# cv-display.net
KiCad netlist of a schematic drawn in EAGLE
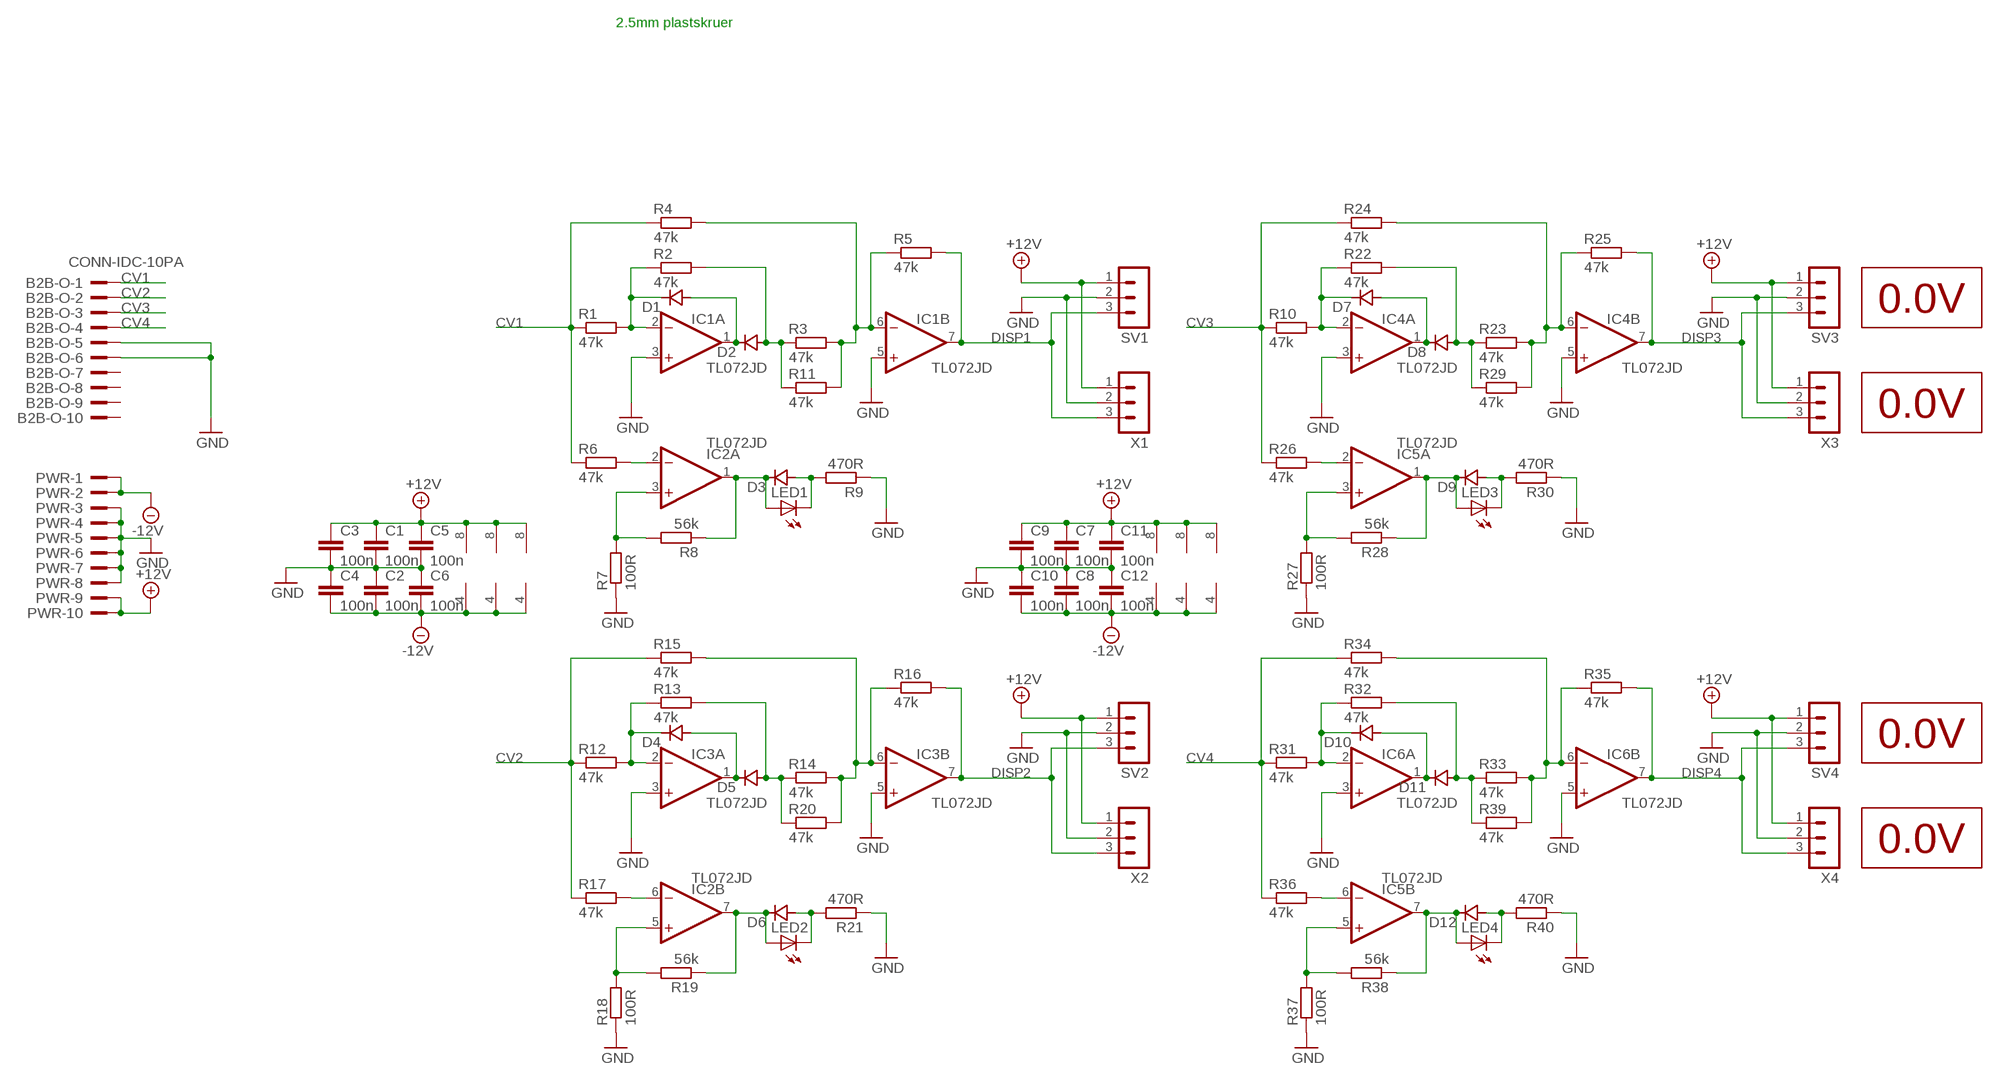
[diagram p0: schematic, sheet 1]

(export (version "E")
  (design (tool "Eeschema 10.0.6"))
  (components
    (comp (ref "B2B-O")
      (value "CONN-IDC-10PA")
      (footprint "eagle-import:CONN-IDC10P-A")
      (libsource (lib "eagle-import") (part "CONN-IDC-10PA"))
    )
    (comp (ref "C1")
      (value "100n")
      (footprint "eagle-import:C0603")
      (libsource (lib "eagle-import") (part "C-EUC0603"))
    )
    (comp (ref "C2")
      (value "100n")
      (footprint "eagle-import:C0603")
      (libsource (lib "eagle-import") (part "C-EUC0603"))
    )
    (comp (ref "C3")
      (value "100n")
      (footprint "eagle-import:C0603")
      (libsource (lib "eagle-import") (part "C-EUC0603"))
    )
    (comp (ref "C4")
      (value "100n")
      (footprint "eagle-import:C0603")
      (libsource (lib "eagle-import") (part "C-EUC0603"))
    )
    (comp (ref "C5")
      (value "100n")
      (footprint "eagle-import:C0603")
      (libsource (lib "eagle-import") (part "C-EUC0603"))
    )
    (comp (ref "C6")
      (value "100n")
      (footprint "eagle-import:C0603")
      (libsource (lib "eagle-import") (part "C-EUC0603"))
    )
    (comp (ref "C7")
      (value "100n")
      (footprint "eagle-import:C0603")
      (libsource (lib "eagle-import") (part "C-EUC0603"))
    )
    (comp (ref "C8")
      (value "100n")
      (footprint "eagle-import:C0603")
      (libsource (lib "eagle-import") (part "C-EUC0603"))
    )
    (comp (ref "C9")
      (value "100n")
      (footprint "eagle-import:C0603")
      (libsource (lib "eagle-import") (part "C-EUC0603"))
    )
    (comp (ref "C10")
      (value "100n")
      (footprint "eagle-import:C0603")
      (libsource (lib "eagle-import") (part "C-EUC0603"))
    )
    (comp (ref "C11")
      (value "100n")
      (footprint "eagle-import:C0603")
      (libsource (lib "eagle-import") (part "C-EUC0603"))
    )
    (comp (ref "C12")
      (value "100n")
      (footprint "eagle-import:C0603")
      (libsource (lib "eagle-import") (part "C-EUC0603"))
    )
    (comp (ref "D1")
      (value "1N4148SOD323")
      (footprint "eagle-import:SOD323J")
      (libsource (lib "eagle-import") (part "1N4148SOD323"))
    )
    (comp (ref "D2")
      (value "1N4148SOD323")
      (footprint "eagle-import:SOD323J")
      (libsource (lib "eagle-import") (part "1N4148SOD323"))
    )
    (comp (ref "D3")
      (value "1N4148SOD323")
      (footprint "eagle-import:SOD323J")
      (libsource (lib "eagle-import") (part "1N4148SOD323"))
    )
    (comp (ref "D4")
      (value "1N4148SOD323")
      (footprint "eagle-import:SOD323J")
      (libsource (lib "eagle-import") (part "1N4148SOD323"))
    )
    (comp (ref "D5")
      (value "1N4148SOD323")
      (footprint "eagle-import:SOD323J")
      (libsource (lib "eagle-import") (part "1N4148SOD323"))
    )
    (comp (ref "D6")
      (value "1N4148SOD323")
      (footprint "eagle-import:SOD323J")
      (libsource (lib "eagle-import") (part "1N4148SOD323"))
    )
    (comp (ref "D7")
      (value "1N4148SOD323")
      (footprint "eagle-import:SOD323J")
      (libsource (lib "eagle-import") (part "1N4148SOD323"))
    )
    (comp (ref "D8")
      (value "1N4148SOD323")
      (footprint "eagle-import:SOD323J")
      (libsource (lib "eagle-import") (part "1N4148SOD323"))
    )
    (comp (ref "D9")
      (value "1N4148SOD323")
      (footprint "eagle-import:SOD323J")
      (libsource (lib "eagle-import") (part "1N4148SOD323"))
    )
    (comp (ref "D10")
      (value "1N4148SOD323")
      (footprint "eagle-import:SOD323J")
      (libsource (lib "eagle-import") (part "1N4148SOD323"))
    )
    (comp (ref "D11")
      (value "1N4148SOD323")
      (footprint "eagle-import:SOD323J")
      (libsource (lib "eagle-import") (part "1N4148SOD323"))
    )
    (comp (ref "D12")
      (value "1N4148SOD323")
      (footprint "eagle-import:SOD323J")
      (libsource (lib "eagle-import") (part "1N4148SOD323"))
    )
    (comp (ref "IC1")
      (value "TL072JD")
      (footprint "eagle-import:SO08J")
      (libsource (lib "eagle-import") (part "TL072JD"))
    )
    (comp (ref "IC2")
      (value "TL072JD")
      (footprint "eagle-import:SO08J")
      (libsource (lib "eagle-import") (part "TL072JD"))
    )
    (comp (ref "IC3")
      (value "TL072JD")
      (footprint "eagle-import:SO08J")
      (libsource (lib "eagle-import") (part "TL072JD"))
    )
    (comp (ref "IC4")
      (value "TL072JD")
      (footprint "eagle-import:SO08J")
      (libsource (lib "eagle-import") (part "TL072JD"))
    )
    (comp (ref "IC5")
      (value "TL072JD")
      (footprint "eagle-import:SO08J")
      (libsource (lib "eagle-import") (part "TL072JD"))
    )
    (comp (ref "IC6")
      (value "TL072JD")
      (footprint "eagle-import:SO08J")
      (libsource (lib "eagle-import") (part "TL072JD"))
    )
    (comp (ref "IC7")
      (value "VOLTMETER")
      (footprint "eagle-import:VOLTMETER")
      (libsource (lib "eagle-import") (part "VOLTMETER"))
    )
    (comp (ref "IC8")
      (value "VOLTMETER")
      (footprint "eagle-import:VOLTMETER")
      (libsource (lib "eagle-import") (part "VOLTMETER"))
    )
    (comp (ref "IC9")
      (value "VOLTMETER")
      (footprint "eagle-import:VOLTMETER")
      (libsource (lib "eagle-import") (part "VOLTMETER"))
    )
    (comp (ref "IC10")
      (value "VOLTMETER")
      (footprint "eagle-import:VOLTMETER")
      (libsource (lib "eagle-import") (part "VOLTMETER"))
    )
    (comp (ref "LED1")
      (value "LED_J2X4")
      (footprint "eagle-import:LED2X4-J")
      (libsource (lib "eagle-import") (part "LED_J2X4"))
    )
    (comp (ref "LED2")
      (value "LED_J2X4")
      (footprint "eagle-import:LED2X4-J")
      (libsource (lib "eagle-import") (part "LED_J2X4"))
    )
    (comp (ref "LED3")
      (value "LED_J2X4")
      (footprint "eagle-import:LED2X4-J")
      (libsource (lib "eagle-import") (part "LED_J2X4"))
    )
    (comp (ref "LED4")
      (value "LED_J2X4")
      (footprint "eagle-import:LED2X4-J")
      (libsource (lib "eagle-import") (part "LED_J2X4"))
    )
    (comp (ref "PWR")
      (value "CONN-IDC-10PA")
      (footprint "eagle-import:CONN-IDC10P-A")
      (libsource (lib "eagle-import") (part "CONN-IDC-10PA"))
    )
    (comp (ref "R1")
      (value "47k")
      (footprint "eagle-import:R0603")
      (libsource (lib "eagle-import") (part "R-EU_R0603"))
    )
    (comp (ref "R2")
      (value "47k")
      (footprint "eagle-import:R0603")
      (libsource (lib "eagle-import") (part "R-EU_R0603"))
    )
    (comp (ref "R3")
      (value "47k")
      (footprint "eagle-import:R0603")
      (libsource (lib "eagle-import") (part "R-EU_R0603"))
    )
    (comp (ref "R4")
      (value "47k")
      (footprint "eagle-import:R0603")
      (libsource (lib "eagle-import") (part "R-EU_R0603"))
    )
    (comp (ref "R5")
      (value "47k")
      (footprint "eagle-import:R0603")
      (libsource (lib "eagle-import") (part "R-EU_R0603"))
    )
    (comp (ref "R6")
      (value "47k")
      (footprint "eagle-import:R0603")
      (libsource (lib "eagle-import") (part "R-EU_R0603"))
    )
    (comp (ref "R7")
      (value "100R")
      (footprint "eagle-import:R0603")
      (libsource (lib "eagle-import") (part "R-EU_R0603"))
    )
    (comp (ref "R8")
      (value "56k")
      (footprint "eagle-import:R0603")
      (libsource (lib "eagle-import") (part "R-EU_R0603"))
    )
    (comp (ref "R9")
      (value "470R")
      (footprint "eagle-import:R0603")
      (libsource (lib "eagle-import") (part "R-EU_R0603"))
    )
    (comp (ref "R10")
      (value "47k")
      (footprint "eagle-import:R0603")
      (libsource (lib "eagle-import") (part "R-EU_R0603"))
    )
    (comp (ref "R11")
      (value "47k")
      (footprint "eagle-import:R0603")
      (libsource (lib "eagle-import") (part "R-EU_R0603"))
    )
    (comp (ref "R12")
      (value "47k")
      (footprint "eagle-import:R0603")
      (libsource (lib "eagle-import") (part "R-EU_R0603"))
    )
    (comp (ref "R13")
      (value "47k")
      (footprint "eagle-import:R0603")
      (libsource (lib "eagle-import") (part "R-EU_R0603"))
    )
    (comp (ref "R14")
      (value "47k")
      (footprint "eagle-import:R0603")
      (libsource (lib "eagle-import") (part "R-EU_R0603"))
    )
    (comp (ref "R15")
      (value "47k")
      (footprint "eagle-import:R0603")
      (libsource (lib "eagle-import") (part "R-EU_R0603"))
    )
    (comp (ref "R16")
      (value "47k")
      (footprint "eagle-import:R0603")
      (libsource (lib "eagle-import") (part "R-EU_R0603"))
    )
    (comp (ref "R17")
      (value "47k")
      (footprint "eagle-import:R0603")
      (libsource (lib "eagle-import") (part "R-EU_R0603"))
    )
    (comp (ref "R18")
      (value "100R")
      (footprint "eagle-import:R0603")
      (libsource (lib "eagle-import") (part "R-EU_R0603"))
    )
    (comp (ref "R19")
      (value "56k")
      (footprint "eagle-import:R0603")
      (libsource (lib "eagle-import") (part "R-EU_R0603"))
    )
    (comp (ref "R20")
      (value "47k")
      (footprint "eagle-import:R0603")
      (libsource (lib "eagle-import") (part "R-EU_R0603"))
    )
    (comp (ref "R21")
      (value "470R")
      (footprint "eagle-import:R0603")
      (libsource (lib "eagle-import") (part "R-EU_R0603"))
    )
    (comp (ref "R22")
      (value "47k")
      (footprint "eagle-import:R0603")
      (libsource (lib "eagle-import") (part "R-EU_R0603"))
    )
    (comp (ref "R23")
      (value "47k")
      (footprint "eagle-import:R0603")
      (libsource (lib "eagle-import") (part "R-EU_R0603"))
    )
    (comp (ref "R24")
      (value "47k")
      (footprint "eagle-import:R0603")
      (libsource (lib "eagle-import") (part "R-EU_R0603"))
    )
    (comp (ref "R25")
      (value "47k")
      (footprint "eagle-import:R0603")
      (libsource (lib "eagle-import") (part "R-EU_R0603"))
    )
    (comp (ref "R26")
      (value "47k")
      (footprint "eagle-import:R0603")
      (libsource (lib "eagle-import") (part "R-EU_R0603"))
    )
    (comp (ref "R27")
      (value "100R")
      (footprint "eagle-import:R0603")
      (libsource (lib "eagle-import") (part "R-EU_R0603"))
    )
    (comp (ref "R28")
      (value "56k")
      (footprint "eagle-import:R0603")
      (libsource (lib "eagle-import") (part "R-EU_R0603"))
    )
    (comp (ref "R29")
      (value "47k")
      (footprint "eagle-import:R0603")
      (libsource (lib "eagle-import") (part "R-EU_R0603"))
    )
    (comp (ref "R30")
      (value "470R")
      (footprint "eagle-import:R0603")
      (libsource (lib "eagle-import") (part "R-EU_R0603"))
    )
    (comp (ref "R31")
      (value "47k")
      (footprint "eagle-import:R0603")
      (libsource (lib "eagle-import") (part "R-EU_R0603"))
    )
    (comp (ref "R32")
      (value "47k")
      (footprint "eagle-import:R0603")
      (libsource (lib "eagle-import") (part "R-EU_R0603"))
    )
    (comp (ref "R33")
      (value "47k")
      (footprint "eagle-import:R0603")
      (libsource (lib "eagle-import") (part "R-EU_R0603"))
    )
    (comp (ref "R34")
      (value "47k")
      (footprint "eagle-import:R0603")
      (libsource (lib "eagle-import") (part "R-EU_R0603"))
    )
    (comp (ref "R35")
      (value "47k")
      (footprint "eagle-import:R0603")
      (libsource (lib "eagle-import") (part "R-EU_R0603"))
    )
    (comp (ref "R36")
      (value "47k")
      (footprint "eagle-import:R0603")
      (libsource (lib "eagle-import") (part "R-EU_R0603"))
    )
    (comp (ref "R37")
      (value "100R")
      (footprint "eagle-import:R0603")
      (libsource (lib "eagle-import") (part "R-EU_R0603"))
    )
    (comp (ref "R38")
      (value "56k")
      (footprint "eagle-import:R0603")
      (libsource (lib "eagle-import") (part "R-EU_R0603"))
    )
    (comp (ref "R39")
      (value "47k")
      (footprint "eagle-import:R0603")
      (libsource (lib "eagle-import") (part "R-EU_R0603"))
    )
    (comp (ref "R40")
      (value "470R")
      (footprint "eagle-import:R0603")
      (libsource (lib "eagle-import") (part "R-EU_R0603"))
    )
    (comp (ref "SV1")
      (value "MA03-1JC")
      (footprint "eagle-import:MA03-1J")
      (libsource (lib "eagle-import") (part "MA03-1JC"))
    )
    (comp (ref "SV2")
      (value "MA03-1JC")
      (footprint "eagle-import:MA03-1J")
      (libsource (lib "eagle-import") (part "MA03-1JC"))
    )
    (comp (ref "SV3")
      (value "MA03-1JC")
      (footprint "eagle-import:MA03-1J")
      (libsource (lib "eagle-import") (part "MA03-1JC"))
    )
    (comp (ref "SV4")
      (value "MA03-1JC")
      (footprint "eagle-import:MA03-1J")
      (libsource (lib "eagle-import") (part "MA03-1JC"))
    )
    (comp (ref "X1")
      (value "WJ300V-5.0-3P")
      (footprint "eagle-import:WJ300V-5.0-3P")
      (libsource (lib "eagle-import") (part "WJ300V-5.0-3P"))
    )
    (comp (ref "X2")
      (value "WJ300V-5.0-3P")
      (footprint "eagle-import:WJ300V-5.0-3P")
      (libsource (lib "eagle-import") (part "WJ300V-5.0-3P"))
    )
    (comp (ref "X3")
      (value "WJ300V-5.0-3P")
      (footprint "eagle-import:WJ300V-5.0-3P")
      (libsource (lib "eagle-import") (part "WJ300V-5.0-3P"))
    )
    (comp (ref "X4")
      (value "WJ300V-5.0-3P")
      (footprint "eagle-import:WJ300V-5.0-3P")
      (libsource (lib "eagle-import") (part "WJ300V-5.0-3P"))
    )
  )
  (nets
    (net (code "1") (name "+12V") (class "Default")
      (node (ref "C1") (pin "1") (pinfunction "1_1") (pintype "passive"))
      (node (ref "C11") (pin "1") (pinfunction "1_1") (pintype "passive"))
      (node (ref "C3") (pin "1") (pinfunction "1_1") (pintype "passive"))
      (node (ref "C5") (pin "1") (pinfunction "1_1") (pintype "passive"))
      (node (ref "C7") (pin "1") (pinfunction "1_1") (pintype "passive"))
      (node (ref "C9") (pin "1") (pinfunction "1_1") (pintype "passive"))
      (node (ref "IC1") (pin "8") (pinfunction "V+_8") (pintype "power_in"))
      (node (ref "IC2") (pin "8") (pinfunction "V+_8") (pintype "power_in"))
      (node (ref "IC3") (pin "8") (pinfunction "V+_8") (pintype "power_in"))
      (node (ref "IC4") (pin "8") (pinfunction "V+_8") (pintype "power_in"))
      (node (ref "IC5") (pin "8") (pinfunction "V+_8") (pintype "power_in"))
      (node (ref "IC6") (pin "8") (pinfunction "V+_8") (pintype "power_in"))
      (node (ref "PWR") (pin "10") (pinfunction "KL_10") (pintype "passive"))
      (node (ref "PWR") (pin "9") (pinfunction "KL_9") (pintype "passive"))
      (node (ref "SV1") (pin "1") (pinfunction "1_1") (pintype "passive"))
      (node (ref "SV2") (pin "1") (pinfunction "1_1") (pintype "passive"))
      (node (ref "SV3") (pin "1") (pinfunction "1_1") (pintype "passive"))
      (node (ref "SV4") (pin "1") (pinfunction "1_1") (pintype "passive"))
      (node (ref "X1") (pin "1") (pinfunction "1_1") (pintype "passive"))
      (node (ref "X2") (pin "1") (pinfunction "1_1") (pintype "passive"))
      (node (ref "X3") (pin "1") (pinfunction "1_1") (pintype "passive"))
      (node (ref "X4") (pin "1") (pinfunction "1_1") (pintype "passive"))
    )
    (net (code "2") (name "-12V") (class "Default")
      (node (ref "C10") (pin "2") (pinfunction "2_2") (pintype "passive"))
      (node (ref "C12") (pin "2") (pinfunction "2_2") (pintype "passive"))
      (node (ref "C2") (pin "2") (pinfunction "2_2") (pintype "passive"))
      (node (ref "C4") (pin "2") (pinfunction "2_2") (pintype "passive"))
      (node (ref "C6") (pin "2") (pinfunction "2_2") (pintype "passive"))
      (node (ref "C8") (pin "2") (pinfunction "2_2") (pintype "passive"))
      (node (ref "IC1") (pin "4") (pinfunction "V-_4") (pintype "power_in"))
      (node (ref "IC2") (pin "4") (pinfunction "V-_4") (pintype "power_in"))
      (node (ref "IC3") (pin "4") (pinfunction "V-_4") (pintype "power_in"))
      (node (ref "IC4") (pin "4") (pinfunction "V-_4") (pintype "power_in"))
      (node (ref "IC5") (pin "4") (pinfunction "V-_4") (pintype "power_in"))
      (node (ref "IC6") (pin "4") (pinfunction "V-_4") (pintype "power_in"))
      (node (ref "PWR") (pin "1") (pinfunction "KL_1") (pintype "passive"))
      (node (ref "PWR") (pin "2") (pinfunction "KL_2") (pintype "passive"))
    )
    (net (code "3") (name "/CV1") (class "Default")
      (node (ref "B2B-O") (pin "1") (pinfunction "KL_1") (pintype "passive"))
      (node (ref "R1") (pin "1") (pinfunction "1_1") (pintype "passive"))
      (node (ref "R4") (pin "1") (pinfunction "1_1") (pintype "passive"))
      (node (ref "R6") (pin "1") (pinfunction "1_1") (pintype "passive"))
    )
    (net (code "4") (name "/CV2") (class "Default")
      (node (ref "B2B-O") (pin "2") (pinfunction "KL_2") (pintype "passive"))
      (node (ref "R12") (pin "1") (pinfunction "1_1") (pintype "passive"))
      (node (ref "R15") (pin "1") (pinfunction "1_1") (pintype "passive"))
      (node (ref "R17") (pin "1") (pinfunction "1_1") (pintype "passive"))
    )
    (net (code "5") (name "/CV3") (class "Default")
      (node (ref "B2B-O") (pin "3") (pinfunction "KL_3") (pintype "passive"))
      (node (ref "R10") (pin "1") (pinfunction "1_1") (pintype "passive"))
      (node (ref "R24") (pin "1") (pinfunction "1_1") (pintype "passive"))
      (node (ref "R26") (pin "1") (pinfunction "1_1") (pintype "passive"))
    )
    (net (code "6") (name "/CV4") (class "Default")
      (node (ref "B2B-O") (pin "4") (pinfunction "KL_4") (pintype "passive"))
      (node (ref "R31") (pin "1") (pinfunction "1_1") (pintype "passive"))
      (node (ref "R34") (pin "1") (pinfunction "1_1") (pintype "passive"))
      (node (ref "R36") (pin "1") (pinfunction "1_1") (pintype "passive"))
    )
    (net (code "7") (name "/DISP1") (class "Default")
      (node (ref "IC1") (pin "7") (pinfunction "OUT_7") (pintype "output"))
      (node (ref "R5") (pin "2") (pinfunction "2_2") (pintype "passive"))
      (node (ref "SV1") (pin "3") (pinfunction "3_3") (pintype "passive"))
      (node (ref "X1") (pin "3") (pinfunction "3_3") (pintype "passive"))
    )
    (net (code "8") (name "/DISP2") (class "Default")
      (node (ref "IC3") (pin "7") (pinfunction "OUT_7") (pintype "output"))
      (node (ref "R16") (pin "2") (pinfunction "2_2") (pintype "passive"))
      (node (ref "SV2") (pin "3") (pinfunction "3_3") (pintype "passive"))
      (node (ref "X2") (pin "3") (pinfunction "3_3") (pintype "passive"))
    )
    (net (code "9") (name "/DISP3") (class "Default")
      (node (ref "IC4") (pin "7") (pinfunction "OUT_7") (pintype "output"))
      (node (ref "R25") (pin "2") (pinfunction "2_2") (pintype "passive"))
      (node (ref "SV3") (pin "3") (pinfunction "3_3") (pintype "passive"))
      (node (ref "X3") (pin "3") (pinfunction "3_3") (pintype "passive"))
    )
    (net (code "10") (name "/DISP4") (class "Default")
      (node (ref "IC6") (pin "7") (pinfunction "OUT_7") (pintype "output"))
      (node (ref "R35") (pin "2") (pinfunction "2_2") (pintype "passive"))
      (node (ref "SV4") (pin "3") (pinfunction "3_3") (pintype "passive"))
      (node (ref "X4") (pin "3") (pinfunction "3_3") (pintype "passive"))
    )
    (net (code "11") (name "GND") (class "Default")
      (node (ref "B2B-O") (pin "5") (pinfunction "KL_5") (pintype "passive"))
      (node (ref "B2B-O") (pin "6") (pinfunction "KL_6") (pintype "passive"))
      (node (ref "C1") (pin "2") (pinfunction "2_2") (pintype "passive"))
      (node (ref "C10") (pin "1") (pinfunction "1_1") (pintype "passive"))
      (node (ref "C11") (pin "2") (pinfunction "2_2") (pintype "passive"))
      (node (ref "C12") (pin "1") (pinfunction "1_1") (pintype "passive"))
      (node (ref "C2") (pin "1") (pinfunction "1_1") (pintype "passive"))
      (node (ref "C3") (pin "2") (pinfunction "2_2") (pintype "passive"))
      (node (ref "C4") (pin "1") (pinfunction "1_1") (pintype "passive"))
      (node (ref "C5") (pin "2") (pinfunction "2_2") (pintype "passive"))
      (node (ref "C6") (pin "1") (pinfunction "1_1") (pintype "passive"))
      (node (ref "C7") (pin "2") (pinfunction "2_2") (pintype "passive"))
      (node (ref "C8") (pin "1") (pinfunction "1_1") (pintype "passive"))
      (node (ref "C9") (pin "2") (pinfunction "2_2") (pintype "passive"))
      (node (ref "IC1") (pin "3") (pinfunction "+IN_3") (pintype "input"))
      (node (ref "IC1") (pin "5") (pinfunction "+IN_5") (pintype "input"))
      (node (ref "IC3") (pin "3") (pinfunction "+IN_3") (pintype "input"))
      (node (ref "IC3") (pin "5") (pinfunction "+IN_5") (pintype "input"))
      (node (ref "IC4") (pin "3") (pinfunction "+IN_3") (pintype "input"))
      (node (ref "IC4") (pin "5") (pinfunction "+IN_5") (pintype "input"))
      (node (ref "IC6") (pin "3") (pinfunction "+IN_3") (pintype "input"))
      (node (ref "IC6") (pin "5") (pinfunction "+IN_5") (pintype "input"))
      (node (ref "PWR") (pin "3") (pinfunction "KL_3") (pintype "passive"))
      (node (ref "PWR") (pin "4") (pinfunction "KL_4") (pintype "passive"))
      (node (ref "PWR") (pin "5") (pinfunction "KL_5") (pintype "passive"))
      (node (ref "PWR") (pin "6") (pinfunction "KL_6") (pintype "passive"))
      (node (ref "PWR") (pin "7") (pinfunction "KL_7") (pintype "passive"))
      (node (ref "PWR") (pin "8") (pinfunction "KL_8") (pintype "passive"))
      (node (ref "R18") (pin "1") (pinfunction "1_1") (pintype "passive"))
      (node (ref "R21") (pin "1") (pinfunction "1_1") (pintype "passive"))
      (node (ref "R27") (pin "1") (pinfunction "1_1") (pintype "passive"))
      (node (ref "R30") (pin "1") (pinfunction "1_1") (pintype "passive"))
      (node (ref "R37") (pin "1") (pinfunction "1_1") (pintype "passive"))
      (node (ref "R40") (pin "1") (pinfunction "1_1") (pintype "passive"))
      (node (ref "R7") (pin "1") (pinfunction "1_1") (pintype "passive"))
      (node (ref "R9") (pin "1") (pinfunction "1_1") (pintype "passive"))
      (node (ref "SV1") (pin "2") (pinfunction "2_2") (pintype "passive"))
      (node (ref "SV2") (pin "2") (pinfunction "2_2") (pintype "passive"))
      (node (ref "SV3") (pin "2") (pinfunction "2_2") (pintype "passive"))
      (node (ref "SV4") (pin "2") (pinfunction "2_2") (pintype "passive"))
      (node (ref "X1") (pin "2") (pinfunction "2_2") (pintype "passive"))
      (node (ref "X2") (pin "2") (pinfunction "2_2") (pintype "passive"))
      (node (ref "X3") (pin "2") (pinfunction "2_2") (pintype "passive"))
      (node (ref "X4") (pin "2") (pinfunction "2_2") (pintype "passive"))
    )
    (net (code "12") (name "Net-(D1-A)") (class "Default")
      (node (ref "D1") (pin "2") (pinfunction "A_2") (pintype "passive"))
      (node (ref "D2") (pin "1") (pinfunction "C_1") (pintype "passive"))
      (node (ref "IC1") (pin "1") (pinfunction "OUT_1") (pintype "output"))
    )
    (net (code "13") (name "Net-(D1-C)") (class "Default")
      (node (ref "D1") (pin "1") (pinfunction "C_1") (pintype "passive"))
      (node (ref "IC1") (pin "2") (pinfunction "-IN_2") (pintype "input"))
      (node (ref "R1") (pin "2") (pinfunction "2_2") (pintype "passive"))
      (node (ref "R2") (pin "1") (pinfunction "1_1") (pintype "passive"))
    )
    (net (code "14") (name "Net-(D2-A)") (class "Default")
      (node (ref "D2") (pin "2") (pinfunction "A_2") (pintype "passive"))
      (node (ref "R11") (pin "1") (pinfunction "1_1") (pintype "passive"))
      (node (ref "R2") (pin "2") (pinfunction "2_2") (pintype "passive"))
      (node (ref "R3") (pin "1") (pinfunction "1_1") (pintype "passive"))
    )
    (net (code "15") (name "Net-(D3-A)") (class "Default")
      (node (ref "D3") (pin "2") (pinfunction "A_2") (pintype "passive"))
      (node (ref "LED1") (pin "CATHODE") (pinfunction "C_CATHODE") (pintype "passive"))
      (node (ref "R9") (pin "2") (pinfunction "2_2") (pintype "passive"))
    )
    (net (code "16") (name "Net-(D3-C)") (class "Default")
      (node (ref "D3") (pin "1") (pinfunction "C_1") (pintype "passive"))
      (node (ref "IC2") (pin "1") (pinfunction "OUT_1") (pintype "output"))
      (node (ref "LED1") (pin "ANODE") (pinfunction "A_ANODE") (pintype "passive"))
      (node (ref "R8") (pin "1") (pinfunction "1_1") (pintype "passive"))
    )
    (net (code "17") (name "Net-(D4-A)") (class "Default")
      (node (ref "D4") (pin "2") (pinfunction "A_2") (pintype "passive"))
      (node (ref "D5") (pin "1") (pinfunction "C_1") (pintype "passive"))
      (node (ref "IC3") (pin "1") (pinfunction "OUT_1") (pintype "output"))
    )
    (net (code "18") (name "Net-(D4-C)") (class "Default")
      (node (ref "D4") (pin "1") (pinfunction "C_1") (pintype "passive"))
      (node (ref "IC3") (pin "2") (pinfunction "-IN_2") (pintype "input"))
      (node (ref "R12") (pin "2") (pinfunction "2_2") (pintype "passive"))
      (node (ref "R13") (pin "1") (pinfunction "1_1") (pintype "passive"))
    )
    (net (code "19") (name "Net-(D5-A)") (class "Default")
      (node (ref "D5") (pin "2") (pinfunction "A_2") (pintype "passive"))
      (node (ref "R13") (pin "2") (pinfunction "2_2") (pintype "passive"))
      (node (ref "R14") (pin "1") (pinfunction "1_1") (pintype "passive"))
      (node (ref "R20") (pin "1") (pinfunction "1_1") (pintype "passive"))
    )
    (net (code "20") (name "Net-(D6-A)") (class "Default")
      (node (ref "D6") (pin "2") (pinfunction "A_2") (pintype "passive"))
      (node (ref "LED2") (pin "CATHODE") (pinfunction "C_CATHODE") (pintype "passive"))
      (node (ref "R21") (pin "2") (pinfunction "2_2") (pintype "passive"))
    )
    (net (code "21") (name "Net-(D6-C)") (class "Default")
      (node (ref "D6") (pin "1") (pinfunction "C_1") (pintype "passive"))
      (node (ref "IC2") (pin "7") (pinfunction "OUT_7") (pintype "output"))
      (node (ref "LED2") (pin "ANODE") (pinfunction "A_ANODE") (pintype "passive"))
      (node (ref "R19") (pin "1") (pinfunction "1_1") (pintype "passive"))
    )
    (net (code "22") (name "Net-(D7-A)") (class "Default")
      (node (ref "D7") (pin "2") (pinfunction "A_2") (pintype "passive"))
      (node (ref "D8") (pin "1") (pinfunction "C_1") (pintype "passive"))
      (node (ref "IC4") (pin "1") (pinfunction "OUT_1") (pintype "output"))
    )
    (net (code "23") (name "Net-(D7-C)") (class "Default")
      (node (ref "D7") (pin "1") (pinfunction "C_1") (pintype "passive"))
      (node (ref "IC4") (pin "2") (pinfunction "-IN_2") (pintype "input"))
      (node (ref "R10") (pin "2") (pinfunction "2_2") (pintype "passive"))
      (node (ref "R22") (pin "1") (pinfunction "1_1") (pintype "passive"))
    )
    (net (code "24") (name "Net-(D8-A)") (class "Default")
      (node (ref "D8") (pin "2") (pinfunction "A_2") (pintype "passive"))
      (node (ref "R22") (pin "2") (pinfunction "2_2") (pintype "passive"))
      (node (ref "R23") (pin "1") (pinfunction "1_1") (pintype "passive"))
      (node (ref "R29") (pin "1") (pinfunction "1_1") (pintype "passive"))
    )
    (net (code "25") (name "Net-(D9-A)") (class "Default")
      (node (ref "D9") (pin "2") (pinfunction "A_2") (pintype "passive"))
      (node (ref "LED3") (pin "CATHODE") (pinfunction "C_CATHODE") (pintype "passive"))
      (node (ref "R30") (pin "2") (pinfunction "2_2") (pintype "passive"))
    )
    (net (code "26") (name "Net-(D9-C)") (class "Default")
      (node (ref "D9") (pin "1") (pinfunction "C_1") (pintype "passive"))
      (node (ref "IC5") (pin "1") (pinfunction "OUT_1") (pintype "output"))
      (node (ref "LED3") (pin "ANODE") (pinfunction "A_ANODE") (pintype "passive"))
      (node (ref "R28") (pin "1") (pinfunction "1_1") (pintype "passive"))
    )
    (net (code "27") (name "Net-(D10-A)") (class "Default")
      (node (ref "D10") (pin "2") (pinfunction "A_2") (pintype "passive"))
      (node (ref "D11") (pin "1") (pinfunction "C_1") (pintype "passive"))
      (node (ref "IC6") (pin "1") (pinfunction "OUT_1") (pintype "output"))
    )
    (net (code "28") (name "Net-(D10-C)") (class "Default")
      (node (ref "D10") (pin "1") (pinfunction "C_1") (pintype "passive"))
      (node (ref "IC6") (pin "2") (pinfunction "-IN_2") (pintype "input"))
      (node (ref "R31") (pin "2") (pinfunction "2_2") (pintype "passive"))
      (node (ref "R32") (pin "1") (pinfunction "1_1") (pintype "passive"))
    )
    (net (code "29") (name "Net-(D11-A)") (class "Default")
      (node (ref "D11") (pin "2") (pinfunction "A_2") (pintype "passive"))
      (node (ref "R32") (pin "2") (pinfunction "2_2") (pintype "passive"))
      (node (ref "R33") (pin "1") (pinfunction "1_1") (pintype "passive"))
      (node (ref "R39") (pin "1") (pinfunction "1_1") (pintype "passive"))
    )
    (net (code "30") (name "Net-(D12-A)") (class "Default")
      (node (ref "D12") (pin "2") (pinfunction "A_2") (pintype "passive"))
      (node (ref "LED4") (pin "CATHODE") (pinfunction "C_CATHODE") (pintype "passive"))
      (node (ref "R40") (pin "2") (pinfunction "2_2") (pintype "passive"))
    )
    (net (code "31") (name "Net-(D12-C)") (class "Default")
      (node (ref "D12") (pin "1") (pinfunction "C_1") (pintype "passive"))
      (node (ref "IC5") (pin "7") (pinfunction "OUT_7") (pintype "output"))
      (node (ref "LED4") (pin "ANODE") (pinfunction "A_ANODE") (pintype "passive"))
      (node (ref "R38") (pin "1") (pinfunction "1_1") (pintype "passive"))
    )
    (net (code "32") (name "Net-(IC1B--IN)") (class "Default")
      (node (ref "IC1") (pin "6") (pinfunction "-IN_6") (pintype "input"))
      (node (ref "R11") (pin "2") (pinfunction "2_2") (pintype "passive"))
      (node (ref "R3") (pin "2") (pinfunction "2_2") (pintype "passive"))
      (node (ref "R4") (pin "2") (pinfunction "2_2") (pintype "passive"))
      (node (ref "R5") (pin "1") (pinfunction "1_1") (pintype "passive"))
    )
    (net (code "33") (name "Net-(IC2A-+IN)") (class "Default")
      (node (ref "IC2") (pin "3") (pinfunction "+IN_3") (pintype "input"))
      (node (ref "R7") (pin "2") (pinfunction "2_2") (pintype "passive"))
      (node (ref "R8") (pin "2") (pinfunction "2_2") (pintype "passive"))
    )
    (net (code "34") (name "Net-(IC2A--IN)") (class "Default")
      (node (ref "IC2") (pin "2") (pinfunction "-IN_2") (pintype "input"))
      (node (ref "R6") (pin "2") (pinfunction "2_2") (pintype "passive"))
    )
    (net (code "35") (name "Net-(IC2B-+IN)") (class "Default")
      (node (ref "IC2") (pin "5") (pinfunction "+IN_5") (pintype "input"))
      (node (ref "R18") (pin "2") (pinfunction "2_2") (pintype "passive"))
      (node (ref "R19") (pin "2") (pinfunction "2_2") (pintype "passive"))
    )
    (net (code "36") (name "Net-(IC2B--IN)") (class "Default")
      (node (ref "IC2") (pin "6") (pinfunction "-IN_6") (pintype "input"))
      (node (ref "R17") (pin "2") (pinfunction "2_2") (pintype "passive"))
    )
    (net (code "37") (name "Net-(IC3B--IN)") (class "Default")
      (node (ref "IC3") (pin "6") (pinfunction "-IN_6") (pintype "input"))
      (node (ref "R14") (pin "2") (pinfunction "2_2") (pintype "passive"))
      (node (ref "R15") (pin "2") (pinfunction "2_2") (pintype "passive"))
      (node (ref "R16") (pin "1") (pinfunction "1_1") (pintype "passive"))
      (node (ref "R20") (pin "2") (pinfunction "2_2") (pintype "passive"))
    )
    (net (code "38") (name "Net-(IC4B--IN)") (class "Default")
      (node (ref "IC4") (pin "6") (pinfunction "-IN_6") (pintype "input"))
      (node (ref "R23") (pin "2") (pinfunction "2_2") (pintype "passive"))
      (node (ref "R24") (pin "2") (pinfunction "2_2") (pintype "passive"))
      (node (ref "R25") (pin "1") (pinfunction "1_1") (pintype "passive"))
      (node (ref "R29") (pin "2") (pinfunction "2_2") (pintype "passive"))
    )
    (net (code "39") (name "Net-(IC5A-+IN)") (class "Default")
      (node (ref "IC5") (pin "3") (pinfunction "+IN_3") (pintype "input"))
      (node (ref "R27") (pin "2") (pinfunction "2_2") (pintype "passive"))
      (node (ref "R28") (pin "2") (pinfunction "2_2") (pintype "passive"))
    )
    (net (code "40") (name "Net-(IC5A--IN)") (class "Default")
      (node (ref "IC5") (pin "2") (pinfunction "-IN_2") (pintype "input"))
      (node (ref "R26") (pin "2") (pinfunction "2_2") (pintype "passive"))
    )
    (net (code "41") (name "Net-(IC5B-+IN)") (class "Default")
      (node (ref "IC5") (pin "5") (pinfunction "+IN_5") (pintype "input"))
      (node (ref "R37") (pin "2") (pinfunction "2_2") (pintype "passive"))
      (node (ref "R38") (pin "2") (pinfunction "2_2") (pintype "passive"))
    )
    (net (code "42") (name "Net-(IC5B--IN)") (class "Default")
      (node (ref "IC5") (pin "6") (pinfunction "-IN_6") (pintype "input"))
      (node (ref "R36") (pin "2") (pinfunction "2_2") (pintype "passive"))
    )
    (net (code "43") (name "Net-(IC6B--IN)") (class "Default")
      (node (ref "IC6") (pin "6") (pinfunction "-IN_6") (pintype "input"))
      (node (ref "R33") (pin "2") (pinfunction "2_2") (pintype "passive"))
      (node (ref "R34") (pin "2") (pinfunction "2_2") (pintype "passive"))
      (node (ref "R35") (pin "1") (pinfunction "1_1") (pintype "passive"))
      (node (ref "R39") (pin "2") (pinfunction "2_2") (pintype "passive"))
    )
    (net (code "44") (name "unconnected-(B2B-OB-KL-Pad10)") (class "Default")
      (node (ref "B2B-O") (pin "10") (pinfunction "KL_10") (pintype "passive"))
    )
    (net (code "45") (name "unconnected-(B2B-OH-KL-Pad7)") (class "Default")
      (node (ref "B2B-O") (pin "7") (pinfunction "KL_7") (pintype "passive"))
    )
    (net (code "46") (name "unconnected-(B2B-OI-KL-Pad8)") (class "Default")
      (node (ref "B2B-O") (pin "8") (pinfunction "KL_8") (pintype "passive"))
    )
    (net (code "47") (name "unconnected-(B2B-OJ-KL-Pad9)") (class "Default")
      (node (ref "B2B-O") (pin "9") (pinfunction "KL_9") (pintype "passive"))
    )
  )
)
